# Keyboard_ribbon_connection.net
KiCad netlist of a schematic drawn in EAGLE
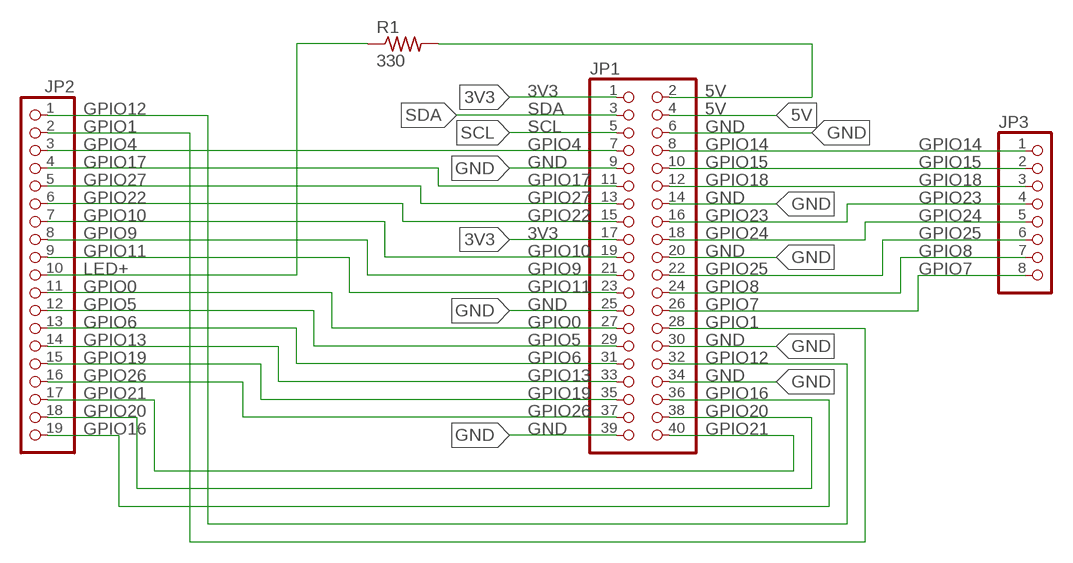
[diagram p0: schematic, sheet 1]

(export (version "E")
  (design (tool "Eeschema 10.0.6"))
  (components
    (comp (ref "JP1")
      (value "PINHD-2X20")
      (footprint "eagle-import:2X20")
      (libsource (lib "eagle-import") (part "PINHD-2X20"))
    )
    (comp (ref "JP2")
      (value "PINHD-1X19")
      (footprint "eagle-import:1X19")
      (libsource (lib "eagle-import") (part "PINHD-1X19"))
    )
    (comp (ref "JP3")
      (value "PINHD-1X8")
      (footprint "eagle-import:1X08")
      (libsource (lib "eagle-import") (part "PINHD-1X8"))
    )
    (comp (ref "R1")
      (value "330")
      (footprint "eagle-import:0207_10")
      (libsource (lib "eagle-import") (part "R-US_0207/10"))
    )
  )
  (nets
    (net (code "1") (name "/GPIO0") (class "Default")
      (node (ref "JP1") (pin "27") (pinfunction "27_27") (pintype "passive"))
      (node (ref "JP2") (pin "11") (pinfunction "11_11") (pintype "passive"))
    )
    (net (code "2") (name "/GPIO1") (class "Default")
      (node (ref "JP1") (pin "28") (pinfunction "28_28") (pintype "passive"))
      (node (ref "JP2") (pin "2") (pinfunction "2_2") (pintype "passive"))
    )
    (net (code "3") (name "/GPIO4") (class "Default")
      (node (ref "JP1") (pin "7") (pinfunction "7_7") (pintype "passive"))
      (node (ref "JP2") (pin "3") (pinfunction "3_3") (pintype "passive"))
    )
    (net (code "4") (name "/GPIO5") (class "Default")
      (node (ref "JP1") (pin "29") (pinfunction "29_29") (pintype "passive"))
      (node (ref "JP2") (pin "12") (pinfunction "12_12") (pintype "passive"))
    )
    (net (code "5") (name "/GPIO6") (class "Default")
      (node (ref "JP1") (pin "31") (pinfunction "31_31") (pintype "passive"))
      (node (ref "JP2") (pin "13") (pinfunction "13_13") (pintype "passive"))
    )
    (net (code "6") (name "/GPIO7") (class "Default")
      (node (ref "JP1") (pin "26") (pinfunction "26_26") (pintype "passive"))
      (node (ref "JP3") (pin "8") (pinfunction "8_8") (pintype "passive"))
    )
    (net (code "7") (name "/GPIO8") (class "Default")
      (node (ref "JP1") (pin "24") (pinfunction "24_24") (pintype "passive"))
      (node (ref "JP3") (pin "7") (pinfunction "7_7") (pintype "passive"))
    )
    (net (code "8") (name "/GPIO9") (class "Default")
      (node (ref "JP1") (pin "21") (pinfunction "21_21") (pintype "passive"))
      (node (ref "JP2") (pin "8") (pinfunction "8_8") (pintype "passive"))
    )
    (net (code "9") (name "/GPIO10") (class "Default")
      (node (ref "JP1") (pin "19") (pinfunction "19_19") (pintype "passive"))
      (node (ref "JP2") (pin "7") (pinfunction "7_7") (pintype "passive"))
    )
    (net (code "10") (name "/GPIO11") (class "Default")
      (node (ref "JP1") (pin "23") (pinfunction "23_23") (pintype "passive"))
      (node (ref "JP2") (pin "9") (pinfunction "9_9") (pintype "passive"))
    )
    (net (code "11") (name "/GPIO12") (class "Default")
      (node (ref "JP1") (pin "32") (pinfunction "32_32") (pintype "passive"))
      (node (ref "JP2") (pin "1") (pinfunction "1_1") (pintype "passive"))
    )
    (net (code "12") (name "/GPIO13") (class "Default")
      (node (ref "JP1") (pin "33") (pinfunction "33_33") (pintype "passive"))
      (node (ref "JP2") (pin "14") (pinfunction "14_14") (pintype "passive"))
    )
    (net (code "13") (name "/GPIO14") (class "Default")
      (node (ref "JP1") (pin "8") (pinfunction "8_8") (pintype "passive"))
      (node (ref "JP3") (pin "1") (pinfunction "1_1") (pintype "passive"))
    )
    (net (code "14") (name "/GPIO15") (class "Default")
      (node (ref "JP1") (pin "10") (pinfunction "10_10") (pintype "passive"))
      (node (ref "JP3") (pin "2") (pinfunction "2_2") (pintype "passive"))
    )
    (net (code "15") (name "/GPIO16") (class "Default")
      (node (ref "JP1") (pin "36") (pinfunction "36_36") (pintype "passive"))
      (node (ref "JP2") (pin "19") (pinfunction "19_19") (pintype "passive"))
    )
    (net (code "16") (name "/GPIO17") (class "Default")
      (node (ref "JP1") (pin "11") (pinfunction "11_11") (pintype "passive"))
      (node (ref "JP2") (pin "4") (pinfunction "4_4") (pintype "passive"))
    )
    (net (code "17") (name "/GPIO18") (class "Default")
      (node (ref "JP1") (pin "12") (pinfunction "12_12") (pintype "passive"))
      (node (ref "JP3") (pin "3") (pinfunction "3_3") (pintype "passive"))
    )
    (net (code "18") (name "/GPIO19") (class "Default")
      (node (ref "JP1") (pin "35") (pinfunction "35_35") (pintype "passive"))
      (node (ref "JP2") (pin "15") (pinfunction "15_15") (pintype "passive"))
    )
    (net (code "19") (name "/GPIO20") (class "Default")
      (node (ref "JP1") (pin "38") (pinfunction "38_38") (pintype "passive"))
      (node (ref "JP2") (pin "18") (pinfunction "18_18") (pintype "passive"))
    )
    (net (code "20") (name "/GPIO21") (class "Default")
      (node (ref "JP1") (pin "40") (pinfunction "40_40") (pintype "passive"))
      (node (ref "JP2") (pin "17") (pinfunction "17_17") (pintype "passive"))
    )
    (net (code "21") (name "/GPIO22") (class "Default")
      (node (ref "JP1") (pin "15") (pinfunction "15_15") (pintype "passive"))
      (node (ref "JP2") (pin "6") (pinfunction "6_6") (pintype "passive"))
    )
    (net (code "22") (name "/GPIO23") (class "Default")
      (node (ref "JP1") (pin "16") (pinfunction "16_16") (pintype "passive"))
      (node (ref "JP3") (pin "4") (pinfunction "4_4") (pintype "passive"))
    )
    (net (code "23") (name "/GPIO24") (class "Default")
      (node (ref "JP1") (pin "18") (pinfunction "18_18") (pintype "passive"))
      (node (ref "JP3") (pin "5") (pinfunction "5_5") (pintype "passive"))
    )
    (net (code "24") (name "/GPIO25") (class "Default")
      (node (ref "JP1") (pin "22") (pinfunction "22_22") (pintype "passive"))
      (node (ref "JP3") (pin "6") (pinfunction "6_6") (pintype "passive"))
    )
    (net (code "25") (name "/GPIO26") (class "Default")
      (node (ref "JP1") (pin "37") (pinfunction "37_37") (pintype "passive"))
      (node (ref "JP2") (pin "16") (pinfunction "16_16") (pintype "passive"))
    )
    (net (code "26") (name "/GPIO27") (class "Default")
      (node (ref "JP1") (pin "13") (pinfunction "13_13") (pintype "passive"))
      (node (ref "JP2") (pin "5") (pinfunction "5_5") (pintype "passive"))
    )
    (net (code "27") (name "/LED+") (class "Default")
      (node (ref "JP2") (pin "10") (pinfunction "10_10") (pintype "passive"))
      (node (ref "R1") (pin "1") (pinfunction "1_1") (pintype "passive"))
    )
    (net (code "28") (name "3V3") (class "Default")
      (node (ref "JP1") (pin "1") (pinfunction "1_1") (pintype "passive"))
      (node (ref "JP1") (pin "17") (pinfunction "17_17") (pintype "passive"))
    )
    (net (code "29") (name "5V") (class "Default")
      (node (ref "JP1") (pin "2") (pinfunction "2_2") (pintype "passive"))
      (node (ref "JP1") (pin "4") (pinfunction "4_4") (pintype "passive"))
      (node (ref "R1") (pin "2") (pinfunction "2_2") (pintype "passive"))
    )
    (net (code "30") (name "GND") (class "Default")
      (node (ref "JP1") (pin "14") (pinfunction "14_14") (pintype "passive"))
      (node (ref "JP1") (pin "20") (pinfunction "20_20") (pintype "passive"))
      (node (ref "JP1") (pin "25") (pinfunction "25_25") (pintype "passive"))
      (node (ref "JP1") (pin "30") (pinfunction "30_30") (pintype "passive"))
      (node (ref "JP1") (pin "34") (pinfunction "34_34") (pintype "passive"))
      (node (ref "JP1") (pin "39") (pinfunction "39_39") (pintype "passive"))
      (node (ref "JP1") (pin "6") (pinfunction "6_6") (pintype "passive"))
      (node (ref "JP1") (pin "9") (pinfunction "9_9") (pintype "passive"))
    )
    (net (code "31") (name "SCL") (class "Default")
      (node (ref "JP1") (pin "5") (pinfunction "5_5") (pintype "passive"))
    )
    (net (code "32") (name "SDA") (class "Default")
      (node (ref "JP1") (pin "3") (pinfunction "3_3") (pintype "passive"))
    )
  )
)
